# TemperatureSensor.net
KiCad netlist of a schematic drawn in Altium Designer
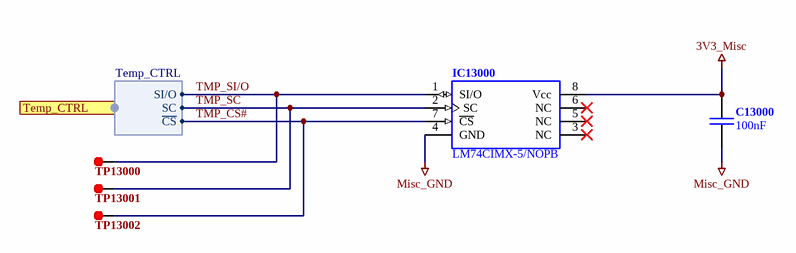
[diagram p0: TemperatureSensor.SchDoc]

(export (version "E")
  (design (tool "Eeschema 10.0.6"))
  (components
    (comp (ref "C13000")
      (value "100nF")
      (footprint "PrometheusLib:C_0603_N [CAPC1608N IPC]")
      (libsource (lib "PrometheusLib") (part "C_GENERIC"))
    )
    (comp (ref "IC13000")
      (value "LM74CIMX-5/NOPB")
      (footprint "SOIC127P600X175-8N IPC")
      (description "SPI 12-Bit Plus Sign Temperature Sensor\r\n0.0625°C Temperature Resolution")
      (libsource (lib "PrometheusLib") (part "IC_LM74CIMX-5/NOPB"))
    )
    (comp (ref "TP13000")
      (value "TP_GENERIC")
      (footprint "PrometheusLib:TP_0.8_P100T")
      (description "Needle Test Point")
      (libsource (lib "PrometheusLib") (part "TP_GENERIC"))
    )
    (comp (ref "TP13001")
      (value "TP_GENERIC")
      (footprint "PrometheusLib:TP_0.8_P100T")
      (description "Needle Test Point")
      (libsource (lib "PrometheusLib") (part "TP_GENERIC"))
    )
    (comp (ref "TP13002")
      (value "TP_GENERIC")
      (footprint "PrometheusLib:TP_0.8_P100T")
      (description "Needle Test Point")
      (libsource (lib "PrometheusLib") (part "TP_GENERIC"))
    )
  )
  (nets
    (net (code "2") (name "/TMP_CS#") (class "Default")
      (node (ref "IC13000") (pin "7") (pinfunction "~{CS}_7") (pintype "input"))
      (node (ref "TP13002") (pin "1") (pinfunction "1_1") (pintype "passive"))
    )
    (net (code "3") (name "/TMP_SC") (class "Default")
      (node (ref "IC13000") (pin "2") (pinfunction "SC_2") (pintype "input"))
      (node (ref "TP13001") (pin "1") (pinfunction "1_1") (pintype "passive"))
    )
    (net (code "4") (name "/TMP_SI{slash}O") (class "Default")
      (node (ref "IC13000") (pin "1") (pinfunction "SI/O_1") (pintype "bidirectional"))
      (node (ref "TP13000") (pin "1") (pinfunction "1_1") (pintype "passive"))
    )
    (net (code "6") (name "3V3_Misc") (class "Default")
      (node (ref "C13000") (pin "1") (pintype "passive"))
      (node (ref "IC13000") (pin "8") (pinfunction "Vcc_8") (pintype "passive"))
    )
    (net (code "7") (name "Misc_GND") (class "Default")
      (node (ref "C13000") (pin "2") (pintype "passive"))
      (node (ref "IC13000") (pin "4") (pinfunction "GND_4") (pintype "passive"))
    )
    (net (code "8") (name "unconnected-(IC13000-NC-Pad3)") (class "Default")
      (node (ref "IC13000") (pin "3") (pinfunction "NC_3") (pintype "passive+no_connect"))
    )
    (net (code "9") (name "unconnected-(IC13000-NC-Pad5)") (class "Default")
      (node (ref "IC13000") (pin "5") (pinfunction "NC_5") (pintype "passive+no_connect"))
    )
    (net (code "10") (name "unconnected-(IC13000-NC-Pad6)") (class "Default")
      (node (ref "IC13000") (pin "6") (pinfunction "NC_6") (pintype "passive+no_connect"))
    )
  )
)
